# mippe_base_v2.net
KiCad netlist of a schematic drawn in EAGLE
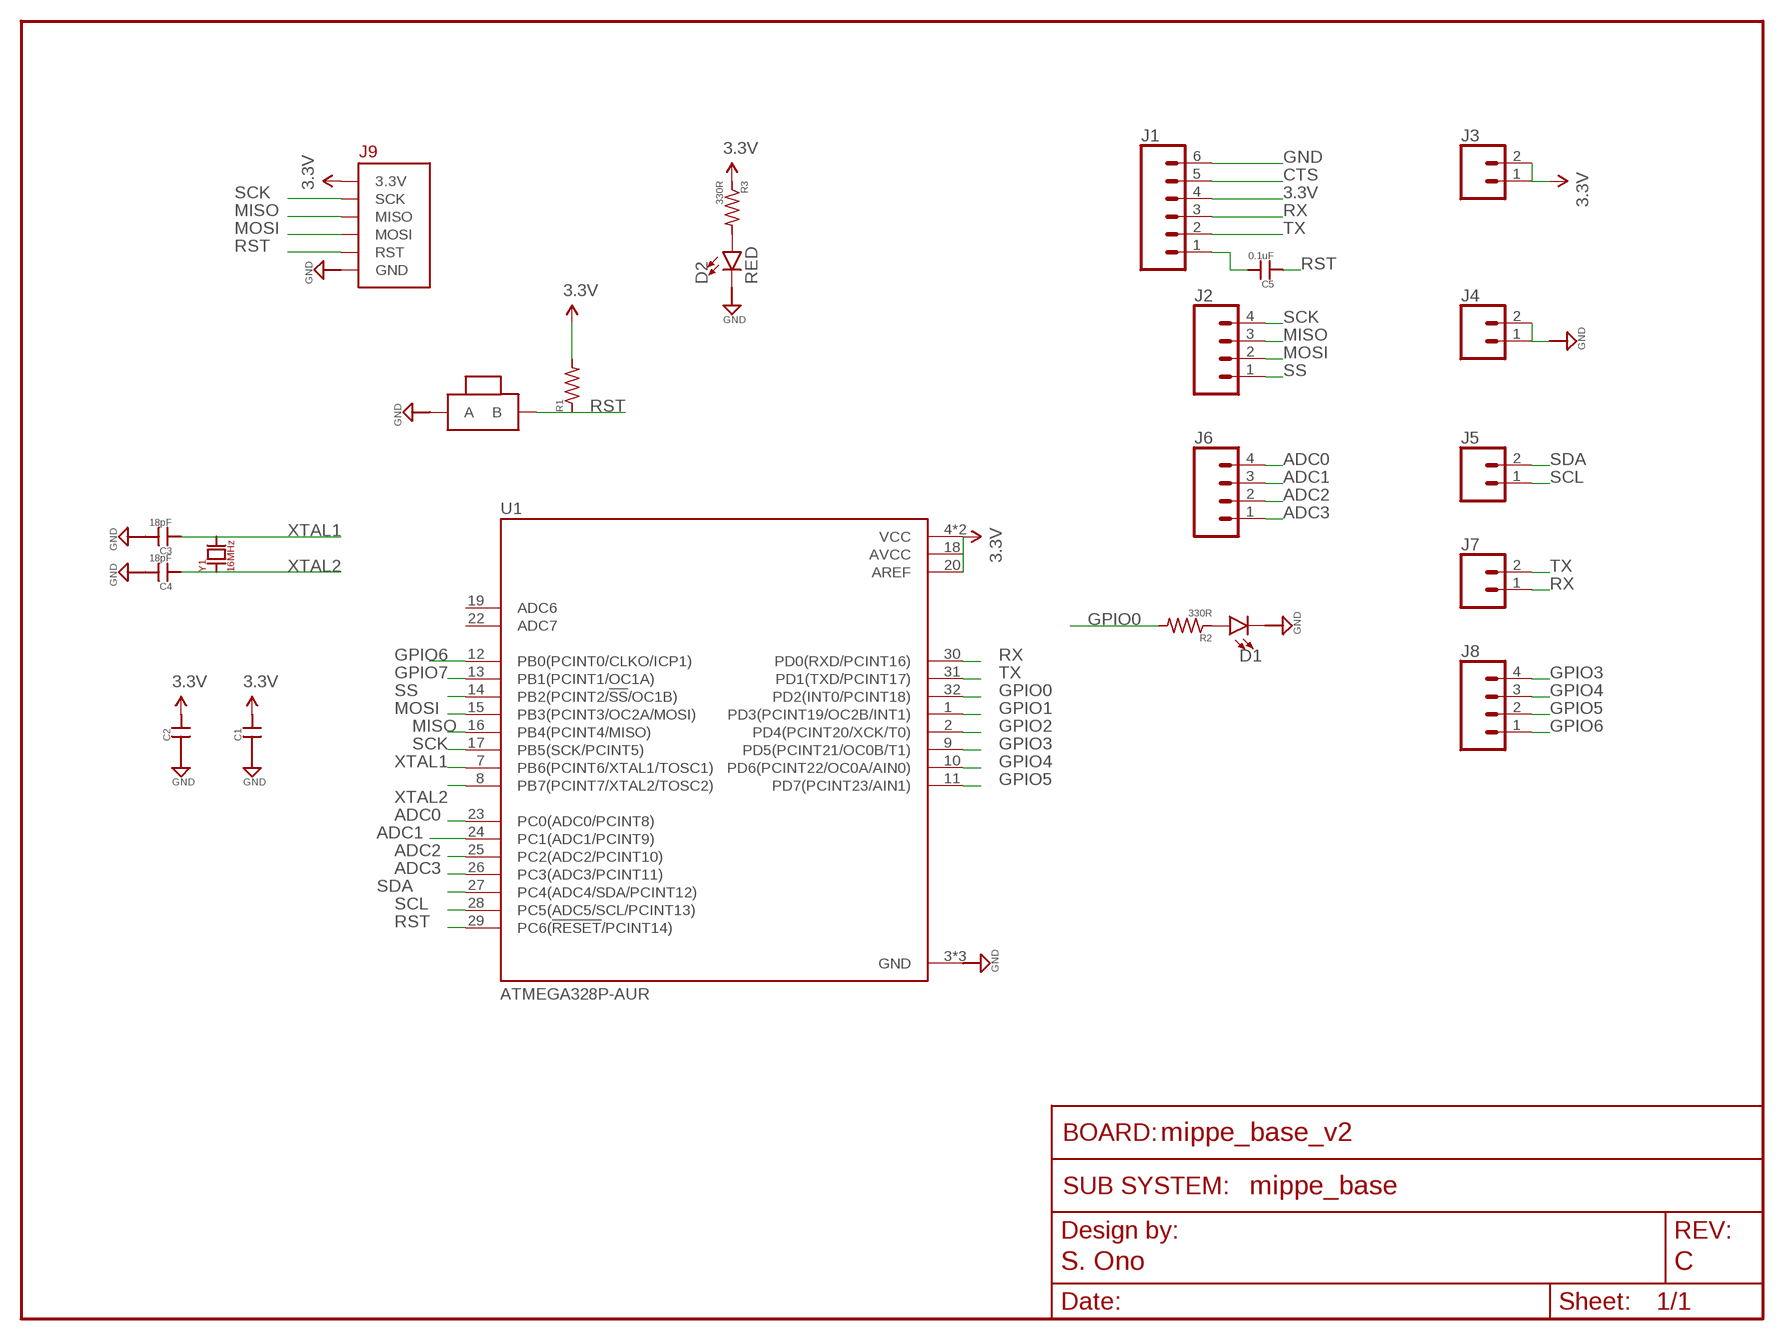
[diagram p0: schematic, sheet 1]

(export (version "E")
  (design (tool "Eeschema 10.0.6"))
  (components
    (comp (ref "C1")
      (value "CAP0603-CAP")
      (footprint "eagle-import:0603-CAP")
      (libsource (lib "eagle-import") (part "CAP0603-CAP"))
    )
    (comp (ref "C2")
      (value "CAP0603-CAP")
      (footprint "eagle-import:0603-CAP")
      (libsource (lib "eagle-import") (part "CAP0603-CAP"))
    )
    (comp (ref "C3")
      (value "18pF")
      (footprint "eagle-import:0603-CAP")
      (libsource (lib "eagle-import") (part "CAP0603-CAP"))
    )
    (comp (ref "C4")
      (value "18pF")
      (footprint "eagle-import:0603-CAP")
      (libsource (lib "eagle-import") (part "CAP0603-CAP"))
    )
    (comp (ref "C5")
      (value "0.1uF")
      (footprint "eagle-import:0603-CAP")
      (libsource (lib "eagle-import") (part "CAP0603-CAP"))
    )
    (comp (ref "D1")
      (value "LED0603")
      (footprint "eagle-import:LED-0603")
      (libsource (lib "eagle-import") (part "LED0603"))
    )
    (comp (ref "D2")
      (value "RED")
      (footprint "eagle-import:LED-0603")
      (libsource (lib "eagle-import") (part "LED0603"))
    )
    (comp (ref "J1")
      (value "CONN_06NO_SILK_FEMALE_PTH")
      (footprint "eagle-import:1X06_NO_SILK")
      (libsource (lib "eagle-import") (part "CONN_06NO_SILK_FEMALE_PTH"))
    )
    (comp (ref "J2")
      (value "CONN_041X04_NO_SILK")
      (footprint "eagle-import:1X04_NO_SILK")
      (libsource (lib "eagle-import") (part "CONN_041X04_NO_SILK"))
    )
    (comp (ref "J3")
      (value "CONN_021X02_NO_SILK")
      (footprint "eagle-import:1X02_NO_SILK")
      (libsource (lib "eagle-import") (part "CONN_021X02_NO_SILK"))
    )
    (comp (ref "J4")
      (value "CONN_021X02_NO_SILK")
      (footprint "eagle-import:1X02_NO_SILK")
      (libsource (lib "eagle-import") (part "CONN_021X02_NO_SILK"))
    )
    (comp (ref "J5")
      (value "CONN_021X02_NO_SILK")
      (footprint "eagle-import:1X02_NO_SILK")
      (libsource (lib "eagle-import") (part "CONN_021X02_NO_SILK"))
    )
    (comp (ref "J6")
      (value "CONN_041X04_NO_SILK")
      (footprint "eagle-import:1X04_NO_SILK")
      (libsource (lib "eagle-import") (part "CONN_041X04_NO_SILK"))
    )
    (comp (ref "J7")
      (value "CONN_021X02_NO_SILK")
      (footprint "eagle-import:1X02_NO_SILK")
      (libsource (lib "eagle-import") (part "CONN_021X02_NO_SILK"))
    )
    (comp (ref "J8")
      (value "CONN_041X04_NO_SILK")
      (footprint "eagle-import:1X04_NO_SILK")
      (libsource (lib "eagle-import") (part "CONN_041X04_NO_SILK"))
    )
    (comp (ref "J9")
      (value "BURNIN")
      (footprint "eagle-import:BURNIN")
      (libsource (lib "eagle-import") (part "BURNIN"))
    )
    (comp (ref "R1")
      (value "R-US_R0603")
      (footprint "eagle-import:R0603")
      (fields (field (name "MANUFACTURER") "Rohm Semiconductor"))
      (libsource (lib "eagle-import") (part "R-US_R0603"))
    )
    (comp (ref "R2")
      (value "330R")
      (footprint "eagle-import:R0603")
      (fields (field (name "MANUFACTURER") "Rohm Semiconductor"))
      (libsource (lib "eagle-import") (part "R-US_R0603"))
    )
    (comp (ref "R3")
      (value "330R")
      (footprint "eagle-import:R0603")
      (fields (field (name "MANUFACTURER") "Rohm Semiconductor"))
      (libsource (lib "eagle-import") (part "R-US_R0603"))
    )
    (comp (ref "SW1")
      (value "BTN-PTS810")
      (footprint "eagle-import:BTN_PTS810")
      (libsource (lib "eagle-import") (part "BTN-PTS810"))
    )
    (comp (ref "U1")
      (value "ATMEGA328P-AUR")
      (footprint "eagle-import:QFP80P900X900X120-32N")
      (fields (field (name "DIGI-KEY_PART_NUMBER") "ATMEGA328P-AURCT-ND") (field (name "MF") "Microchip"))
      (libsource (lib "eagle-import") (part "ATMEGA328P-AUR"))
    )
    (comp (ref "Y1")
      (value "16MHz")
      (footprint "eagle-import:XTAL500X320X130N")
      (libsource (lib "eagle-import") (part "CRYSTAL_SMOL"))
    )
  )
  (nets
    (net (code "1") (name "/ADC0") (class "Default")
      (node (ref "J6") (pin "4") (pinfunction "4_4") (pintype "passive"))
      (node (ref "U1") (pin "23") (pinfunction "PC0(ADC0/PCINT8)_23") (pintype "bidirectional"))
    )
    (net (code "2") (name "/ADC1") (class "Default")
      (node (ref "J6") (pin "3") (pinfunction "3_3") (pintype "passive"))
      (node (ref "U1") (pin "24") (pinfunction "PC1(ADC1/PCINT9)_24") (pintype "bidirectional"))
    )
    (net (code "3") (name "/ADC2") (class "Default")
      (node (ref "J6") (pin "2") (pinfunction "2_2") (pintype "passive"))
      (node (ref "U1") (pin "25") (pinfunction "PC2(ADC2/PCINT10)_25") (pintype "bidirectional"))
    )
    (net (code "4") (name "/ADC3") (class "Default")
      (node (ref "J6") (pin "1") (pinfunction "1_1") (pintype "passive"))
      (node (ref "U1") (pin "26") (pinfunction "PC3(ADC3/PCINT11)_26") (pintype "bidirectional"))
    )
    (net (code "5") (name "/CTS") (class "Default")
      (node (ref "J1") (pin "5") (pinfunction "5_5") (pintype "passive"))
    )
    (net (code "6") (name "/GPIO0") (class "Default")
      (node (ref "R2") (pin "2") (pinfunction "2_2") (pintype "passive"))
      (node (ref "U1") (pin "32") (pinfunction "PD2(INT0/PCINT18)_32") (pintype "bidirectional"))
    )
    (net (code "7") (name "/GPIO1") (class "Default")
      (node (ref "U1") (pin "1") (pinfunction "PD3(PCINT19/OC2B/INT1)_1") (pintype "bidirectional"))
    )
    (net (code "8") (name "/GPIO2") (class "Default")
      (node (ref "U1") (pin "2") (pinfunction "PD4(PCINT20/XCK/T0)_2") (pintype "bidirectional"))
    )
    (net (code "9") (name "/GPIO3") (class "Default")
      (node (ref "J8") (pin "4") (pinfunction "4_4") (pintype "passive"))
      (node (ref "U1") (pin "9") (pinfunction "PD5(PCINT21/OC0B/T1)_9") (pintype "bidirectional"))
    )
    (net (code "10") (name "/GPIO4") (class "Default")
      (node (ref "J8") (pin "3") (pinfunction "3_3") (pintype "passive"))
      (node (ref "U1") (pin "10") (pinfunction "PD6(PCINT22/OC0A/AIN0)_10") (pintype "bidirectional"))
    )
    (net (code "11") (name "/GPIO5") (class "Default")
      (node (ref "J8") (pin "2") (pinfunction "2_2") (pintype "passive"))
      (node (ref "U1") (pin "11") (pinfunction "PD7(PCINT23/AIN1)_11") (pintype "bidirectional"))
    )
    (net (code "12") (name "/GPIO6") (class "Default")
      (node (ref "J8") (pin "1") (pinfunction "1_1") (pintype "passive"))
      (node (ref "U1") (pin "12") (pinfunction "PB0(PCINT0/CLKO/ICP1)_12") (pintype "bidirectional"))
    )
    (net (code "13") (name "/GPIO7") (class "Default")
      (node (ref "U1") (pin "13") (pinfunction "PB1(PCINT1/OC1A)_13") (pintype "bidirectional"))
    )
    (net (code "14") (name "/MISO") (class "Default")
      (node (ref "J2") (pin "3") (pinfunction "3_3") (pintype "passive"))
      (node (ref "J9") (pin "MISO") (pinfunction "MISO_MISO") (pintype "bidirectional"))
      (node (ref "U1") (pin "16") (pinfunction "PB4(PCINT4/MISO)_16") (pintype "bidirectional"))
    )
    (net (code "15") (name "/MOSI") (class "Default")
      (node (ref "J2") (pin "2") (pinfunction "2_2") (pintype "passive"))
      (node (ref "J9") (pin "MOSI") (pinfunction "MOSI_MOSI") (pintype "bidirectional"))
      (node (ref "U1") (pin "15") (pinfunction "PB3(PCINT3/OC2A/MOSI)_15") (pintype "bidirectional"))
    )
    (net (code "16") (name "/RST") (class "Default")
      (node (ref "C5") (pin "1") (pinfunction "1_1") (pintype "passive"))
      (node (ref "J9") (pin "RST") (pinfunction "RST_RST") (pintype "bidirectional"))
      (node (ref "R1") (pin "1") (pinfunction "1_1") (pintype "passive"))
      (node (ref "SW1") (pin "3") (pinfunction "B_3") (pintype "bidirectional"))
      (node (ref "SW1") (pin "4") (pinfunction "B_4") (pintype "bidirectional"))
      (node (ref "U1") (pin "29") (pinfunction "PC6(~{RESET}/PCINT14)_29") (pintype "bidirectional"))
    )
    (net (code "17") (name "/RX") (class "Default")
      (node (ref "J1") (pin "3") (pinfunction "3_3") (pintype "passive"))
      (node (ref "J7") (pin "1") (pinfunction "1_1") (pintype "passive"))
      (node (ref "U1") (pin "30") (pinfunction "PD0(RXD/PCINT16)_30") (pintype "bidirectional"))
    )
    (net (code "18") (name "/SCK") (class "Default")
      (node (ref "J2") (pin "4") (pinfunction "4_4") (pintype "passive"))
      (node (ref "J9") (pin "SCK") (pinfunction "SCK_SCK") (pintype "bidirectional"))
      (node (ref "U1") (pin "17") (pinfunction "PB5(SCK/PCINT5)_17") (pintype "bidirectional"))
    )
    (net (code "19") (name "/SCL") (class "Default")
      (node (ref "J5") (pin "1") (pinfunction "1_1") (pintype "passive"))
      (node (ref "U1") (pin "28") (pinfunction "PC5(ADC5/SCL/PCINT13)_28") (pintype "bidirectional"))
    )
    (net (code "20") (name "/SDA") (class "Default")
      (node (ref "J5") (pin "2") (pinfunction "2_2") (pintype "passive"))
      (node (ref "U1") (pin "27") (pinfunction "PC4(ADC4/SDA/PCINT12)_27") (pintype "bidirectional"))
    )
    (net (code "21") (name "/SS") (class "Default")
      (node (ref "J2") (pin "1") (pinfunction "1_1") (pintype "passive"))
      (node (ref "U1") (pin "14") (pinfunction "PB2(PCINT2/~{SS}/OC1B)_14") (pintype "bidirectional"))
    )
    (net (code "22") (name "/TX") (class "Default")
      (node (ref "J1") (pin "2") (pinfunction "2_2") (pintype "passive"))
      (node (ref "J7") (pin "2") (pinfunction "2_2") (pintype "passive"))
      (node (ref "U1") (pin "31") (pinfunction "PD1(TXD/PCINT17)_31") (pintype "bidirectional"))
    )
    (net (code "23") (name "/XTAL1") (class "Default")
      (node (ref "C3") (pin "1") (pinfunction "1_1") (pintype "passive"))
      (node (ref "U1") (pin "7") (pinfunction "PB6(PCINT6/XTAL1/TOSC1)_7") (pintype "bidirectional"))
      (node (ref "Y1") (pin "2") (pinfunction "B_2") (pintype "passive"))
    )
    (net (code "24") (name "/XTAL2") (class "Default")
      (node (ref "C4") (pin "1") (pinfunction "1_1") (pintype "passive"))
      (node (ref "U1") (pin "8") (pinfunction "PB7(PCINT7/XTAL2/TOSC2)_8") (pintype "bidirectional"))
      (node (ref "Y1") (pin "1") (pinfunction "A_1") (pintype "passive"))
    )
    (net (code "25") (name "3.3V") (class "Default")
      (node (ref "C1") (pin "2") (pinfunction "2_2") (pintype "passive"))
      (node (ref "C2") (pin "2") (pinfunction "2_2") (pintype "passive"))
      (node (ref "J1") (pin "4") (pinfunction "4_4") (pintype "passive"))
      (node (ref "J3") (pin "1") (pinfunction "1_1") (pintype "passive"))
      (node (ref "J3") (pin "2") (pinfunction "2_2") (pintype "passive"))
      (node (ref "J9") (pin "3.3V") (pinfunction "3.3V_3.3V") (pintype "power_in"))
      (node (ref "R1") (pin "2") (pinfunction "2_2") (pintype "passive"))
      (node (ref "R3") (pin "1") (pinfunction "1_1") (pintype "passive"))
      (node (ref "U1") (pin "18") (pinfunction "AVCC_18") (pintype "power_in"))
      (node (ref "U1") (pin "20") (pinfunction "AREF_20") (pintype "power_in"))
      (node (ref "U1") (pin "4") (pinfunction "VCC_4") (pintype "power_in"))
      (node (ref "U1") (pin "6") (pinfunction "VCC_6") (pintype "power_in"))
    )
    (net (code "26") (name "GND") (class "Default")
      (node (ref "C1") (pin "1") (pinfunction "1_1") (pintype "passive"))
      (node (ref "C2") (pin "1") (pinfunction "1_1") (pintype "passive"))
      (node (ref "C3") (pin "2") (pinfunction "2_2") (pintype "passive"))
      (node (ref "C4") (pin "2") (pinfunction "2_2") (pintype "passive"))
      (node (ref "D1") (pin "C") (pinfunction "C_C") (pintype "passive"))
      (node (ref "D2") (pin "C") (pinfunction "C_C") (pintype "passive"))
      (node (ref "J1") (pin "6") (pinfunction "6_6") (pintype "passive"))
      (node (ref "J4") (pin "1") (pinfunction "1_1") (pintype "passive"))
      (node (ref "J4") (pin "2") (pinfunction "2_2") (pintype "passive"))
      (node (ref "J9") (pin "GND") (pinfunction "GND_GND") (pintype "power_in"))
      (node (ref "SW1") (pin "1") (pinfunction "A_1") (pintype "bidirectional"))
      (node (ref "SW1") (pin "2") (pinfunction "A_2") (pintype "bidirectional"))
      (node (ref "U1") (pin "21") (pinfunction "GND_21") (pintype "power_in"))
      (node (ref "U1") (pin "3") (pinfunction "GND_3") (pintype "power_in"))
      (node (ref "U1") (pin "5") (pinfunction "GND_5") (pintype "power_in"))
    )
    (net (code "27") (name "Net-(C5-Pad2)") (class "Default")
      (node (ref "C5") (pin "2") (pinfunction "2_2") (pintype "passive"))
      (node (ref "J1") (pin "1") (pinfunction "1_1") (pintype "passive"))
    )
    (net (code "28") (name "Net-(D1-PadA)") (class "Default")
      (node (ref "D1") (pin "A") (pinfunction "A_A") (pintype "passive"))
      (node (ref "R2") (pin "1") (pinfunction "1_1") (pintype "passive"))
    )
    (net (code "29") (name "Net-(D2-PadA)") (class "Default")
      (node (ref "D2") (pin "A") (pinfunction "A_A") (pintype "passive"))
      (node (ref "R3") (pin "2") (pinfunction "2_2") (pintype "passive"))
    )
    (net (code "30") (name "unconnected-(U1-ADC6-Pad19)") (class "Default")
      (node (ref "U1") (pin "19") (pinfunction "ADC6_19") (pintype "input"))
    )
    (net (code "31") (name "unconnected-(U1-ADC7-Pad22)") (class "Default")
      (node (ref "U1") (pin "22") (pinfunction "ADC7_22") (pintype "input"))
    )
  )
)
